# regulater.net
KiCad netlist of a schematic drawn in Altium Designer
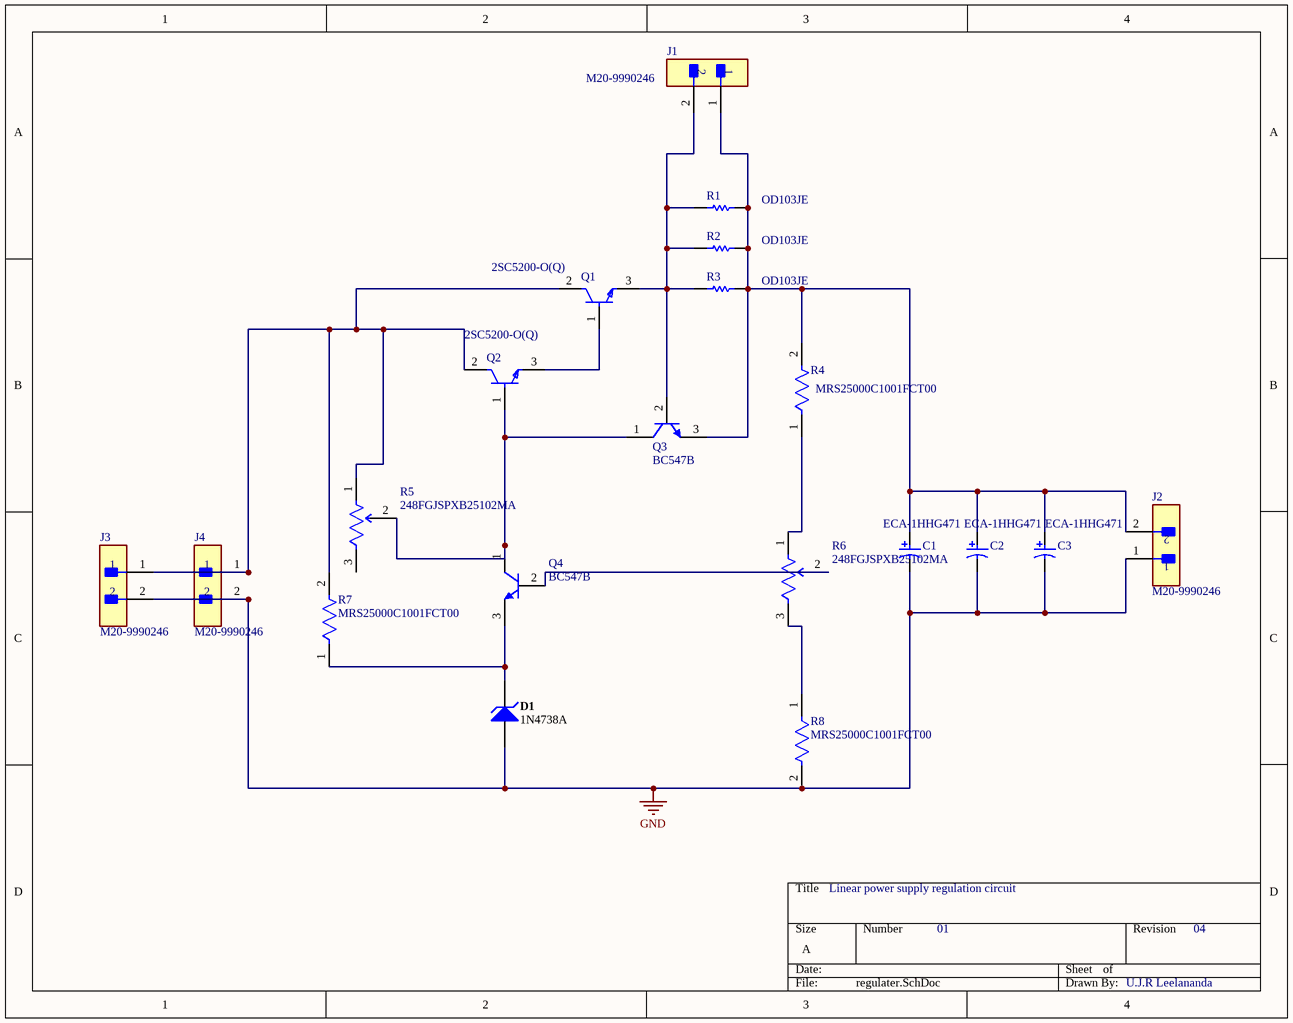
[diagram p0: regulater.SchDoc]

(export (version "E")
  (design (tool "Eeschema 10.0.6"))
  (components
    (comp (ref "C1")
      (value "ECA-1HHG471")
      (footprint "PNSC-CAP-10x20-P2")
      (description "Aluminum Electrolytic Capacitor, 470 uF, +/- 20%, 50 V, -55 to 105 degC, 2-Pin THD, RoHS, Bulk")
      (fields (field (name "MANUFACTURER") "Panasonic"))
      (libsource (lib "Altium Content Vault") (part "CAP-P-2"))
    )
    (comp (ref "C2")
      (value "ECA-1HHG471")
      (footprint "PNSC-CAP-10x20-P2")
      (description "Aluminum Electrolytic Capacitor, 470 uF, +/- 20%, 50 V, -55 to 105 degC, 2-Pin THD, RoHS, Bulk")
      (fields (field (name "MANUFACTURER") "Panasonic"))
      (libsource (lib "Altium Content Vault") (part "CAP-P-2"))
    )
    (comp (ref "C3")
      (value "ECA-1HHG471")
      (footprint "PNSC-CAP-10x20-P2")
      (description "Aluminum Electrolytic Capacitor, 470 uF, +/- 20%, 50 V, -55 to 105 degC, 2-Pin THD, RoHS, Bulk")
      (fields (field (name "MANUFACTURER") "Panasonic"))
      (libsource (lib "Altium Content Vault") (part "CAP-P-2"))
    )
    (comp (ref "D1")
      (value "1N4738A")
      (footprint "FAIR-DO-41-2_V")
      (description "Zener Diode, 8.2V, 1W, 5%, -65 to 200 degC, 2-Pin DO-41, Body 2.72 x 5.2 mm, RoHS")
      (fields (field (name "TOLERANCE") "5%") (field (name "MANUFACTURER") "Fairchild Semiconductor"))
      (libsource (lib "Altium Content Vault") (part "FAIR-DZEN-A1K2-2"))
    )
    (comp (ref "J1")
      (value "M20-9990246")
      (footprint "FP-M20-9990246-MFG")
      (description "CONN HEADER VERT 2POS 2.54MM")
      (fields
        (field (name "OCTOPART") "https://octopart.com/m20-9990246-harwin-2590635")
        (field (name "MANUFACTURER") "Harwin")
      )
      (libsource (lib "") (part "3bc925449376181038e59eaffc5286c_2"))
    )
    (comp (ref "J2")
      (value "M20-9990246")
      (footprint "FP-M20-9990246-MFG")
      (description "CONN HEADER VERT 2POS 2.54MM")
      (fields
        (field (name "OCTOPART") "https://octopart.com/m20-9990246-harwin-2590635")
        (field (name "MANUFACTURER") "Harwin")
      )
      (libsource (lib "") (part "3bc925449376181038e59eaffc5286c_1"))
    )
    (comp (ref "J3")
      (value "M20-9990246")
      (footprint "FP-M20-9990246-MFG")
      (description "CONN HEADER VERT 2POS 2.54MM")
      (fields
        (field (name "OCTOPART") "https://octopart.com/m20-9990246-harwin-2590635")
        (field (name "MANUFACTURER") "Harwin")
      )
      (libsource (lib "Altium Content Vault") (part "3bc925449376181038e59eaffc5286c"))
    )
    (comp (ref "J4")
      (value "M20-9990246")
      (footprint "FP-M20-9990246-MFG")
      (description "CONN HEADER VERT 2POS 2.54MM")
      (fields
        (field (name "OCTOPART") "https://octopart.com/m20-9990246-harwin-2590635")
        (field (name "MANUFACTURER") "Harwin")
      )
      (libsource (lib "Altium Content Vault") (part "3bc925449376181038e59eaffc5286c"))
    )
    (comp (ref "Q1")
      (value "2SC5200-O(Q)")
      (footprint "FP-2-21F1A-MFG")
      (description "TRANS NPN 230V 15A TO-3PL")
      (libsource (lib "Altium Content Vault") (part "00d3c44dadf19597ad74dcf16b45d25"))
    )
    (comp (ref "Q2")
      (value "2SC5200-O(Q)")
      (footprint "FP-2-21F1A-MFG")
      (description "TRANS NPN 230V 15A TO-3PL")
      (libsource (lib "Altium Content Vault") (part "00d3c44dadf19597ad74dcf16b45d25"))
    )
    (comp (ref "Q3")
      (value "BC547B")
      (footprint "ONSC-TO-92-3-29-11")
      (description "Amplifier Transistor, NPN Silicon, 3-Pin TO-92, Bulk Box")
      (fields (field (name "MANUFACTURER") "On Semiconductor"))
      (libsource (lib "Altium Content Vault") (part "ONSC-NPN-C1B2E3-3"))
    )
    (comp (ref "Q4")
      (value "BC547B")
      (footprint "ONSC-TO-92-3-29-11")
      (description "Amplifier Transistor, NPN Silicon, 3-Pin TO-92, Bulk Box")
      (fields (field (name "MANUFACTURER") "On Semiconductor"))
      (libsource (lib "Altium Content Vault") (part "ONSC-NPN-C1B2E3-3"))
    )
    (comp (ref "R1")
      (value "OD103JE")
      (footprint "OMTE-RES7X2.5-2")
      (fields (field (name "TOLERANCE") "±5%") (field (name "MANUFACTURER") "Ohmite"))
      (libsource (lib "Altium Content Vault") (part "RES-2"))
    )
    (comp (ref "R2")
      (value "OD103JE")
      (footprint "OMTE-RES7X2.5-2")
      (fields (field (name "TOLERANCE") "±5%") (field (name "MANUFACTURER") "Ohmite"))
      (libsource (lib "Altium Content Vault") (part "RES-2"))
    )
    (comp (ref "R3")
      (value "OD103JE")
      (footprint "OMTE-RES7X2.5-2")
      (fields (field (name "TOLERANCE") "±5%") (field (name "MANUFACTURER") "Ohmite"))
      (libsource (lib "Altium Content Vault") (part "RES-2"))
    )
    (comp (ref "R4")
      (value "MRS25000C1001FCT00")
      (footprint "FP-MRS25-MFG")
      (description "RES 1K OHM 0.6W 1% AXIAL")
      (fields (field (name "TOLERANCE") "1%"))
      (libsource (lib "Altium Content Vault") (part "1029c3af85768c4190bb7ad29bc67b5"))
    )
    (comp (ref "R5")
      (value "248FGJSPXB25102MA")
      (footprint "FP-248FGJSPXB25102MA-MFG")
      (description "POT PLASTIC LINEAR")
      (fields (field (name "TOLERANCE") "20%"))
      (libsource (lib "Altium Content Vault") (part "1187411b85b29beaefda66c4d54de6f"))
    )
    (comp (ref "R6")
      (value "248FGJSPXB25102MA")
      (footprint "FP-248FGJSPXB25102MA-MFG")
      (description "POT PLASTIC LINEAR")
      (fields (field (name "TOLERANCE") "20%"))
      (libsource (lib "Altium Content Vault") (part "1187411b85b29beaefda66c4d54de6f"))
    )
    (comp (ref "R7")
      (value "MRS25000C1001FCT00")
      (footprint "FP-MRS25-MFG")
      (description "RES 1K OHM 0.6W 1% AXIAL")
      (fields (field (name "TOLERANCE") "1%"))
      (libsource (lib "Altium Content Vault") (part "1029c3af85768c4190bb7ad29bc67b5"))
    )
    (comp (ref "R8")
      (value "MRS25000C1001FCT00")
      (footprint "FP-MRS25-MFG")
      (description "RES 1K OHM 0.6W 1% AXIAL")
      (fields (field (name "TOLERANCE") "1%"))
      (libsource (lib "Altium Content Vault") (part "1029c3af85768c4190bb7ad29bc67b5"))
    )
  )
  (nets
    (net (code "1") (name "GND") (class "Default")
      (node (ref "C1") (pin "2") (pinfunction "2_2") (pintype "passive"))
      (node (ref "C2") (pin "2") (pinfunction "2_2") (pintype "passive"))
      (node (ref "C3") (pin "2") (pinfunction "2_2") (pintype "passive"))
      (node (ref "D1") (pin "1") (pinfunction "A_1") (pintype "passive"))
      (node (ref "J2") (pin "1") (pinfunction "1_1") (pintype "passive"))
      (node (ref "J3") (pin "2") (pinfunction "2_2") (pintype "passive"))
      (node (ref "J4") (pin "2") (pinfunction "2_2") (pintype "passive"))
      (node (ref "R8") (pin "2") (pinfunction "2_2") (pintype "passive"))
    )
    (net (code "2") (name "Net-(D1-K)") (class "Default")
      (node (ref "D1") (pin "2") (pinfunction "K_2") (pintype "passive"))
      (node (ref "Q4") (pin "3") (pinfunction "E_3") (pintype "passive"))
      (node (ref "R7") (pin "1") (pinfunction "1_1") (pintype "passive"))
    )
    (net (code "3") (name "Net-(Q1-B)") (class "Default")
      (node (ref "Q1") (pin "1") (pinfunction "B_1") (pintype "passive"))
      (node (ref "Q2") (pin "3") (pinfunction "E_3") (pintype "passive"))
    )
    (net (code "4") (name "Net-(Q1-C)") (class "Default")
      (node (ref "J3") (pin "1") (pinfunction "1_1") (pintype "passive"))
      (node (ref "J4") (pin "1") (pinfunction "1_1") (pintype "passive"))
      (node (ref "Q1") (pin "2") (pinfunction "C_2") (pintype "passive"))
      (node (ref "Q2") (pin "2") (pinfunction "C_2") (pintype "passive"))
      (node (ref "R5") (pin "1") (pinfunction "1_1") (pintype "passive"))
      (node (ref "R7") (pin "2") (pinfunction "2_2") (pintype "passive"))
    )
    (net (code "5") (name "Net-(Q1-E)") (class "Default")
      (node (ref "J1") (pin "2") (pinfunction "2_2") (pintype "passive"))
      (node (ref "Q1") (pin "3") (pinfunction "E_3") (pintype "passive"))
      (node (ref "Q3") (pin "2") (pinfunction "B_2") (pintype "passive"))
      (node (ref "R1") (pin "1") (pinfunction "1_1") (pintype "passive"))
      (node (ref "R2") (pin "1") (pinfunction "1_1") (pintype "passive"))
      (node (ref "R3") (pin "1") (pinfunction "1_1") (pintype "passive"))
    )
    (net (code "6") (name "Net-(Q2-B)") (class "Default")
      (node (ref "Q2") (pin "1") (pinfunction "B_1") (pintype "passive"))
      (node (ref "Q3") (pin "1") (pinfunction "C_1") (pintype "passive"))
      (node (ref "Q4") (pin "1") (pinfunction "C_1") (pintype "passive"))
      (node (ref "R5") (pin "2") (pinfunction "CW_2") (pintype "passive"))
    )
    (net (code "7") (name "Net-(Q3-E)") (class "Default")
      (node (ref "C1") (pin "1") (pinfunction "1_1") (pintype "passive"))
      (node (ref "C2") (pin "1") (pinfunction "1_1") (pintype "passive"))
      (node (ref "C3") (pin "1") (pinfunction "1_1") (pintype "passive"))
      (node (ref "J1") (pin "1") (pinfunction "1_1") (pintype "passive"))
      (node (ref "J2") (pin "2") (pinfunction "2_2") (pintype "passive"))
      (node (ref "Q3") (pin "3") (pinfunction "E_3") (pintype "passive"))
      (node (ref "R1") (pin "2") (pinfunction "2_2") (pintype "passive"))
      (node (ref "R2") (pin "2") (pinfunction "2_2") (pintype "passive"))
      (node (ref "R3") (pin "2") (pinfunction "2_2") (pintype "passive"))
      (node (ref "R4") (pin "2") (pinfunction "2_2") (pintype "passive"))
    )
    (net (code "8") (name "Net-(Q4-B)") (class "Default")
      (node (ref "Q4") (pin "2") (pinfunction "B_2") (pintype "passive"))
      (node (ref "R6") (pin "2") (pinfunction "CW_2") (pintype "passive"))
    )
    (net (code "9") (name "Net-(R4-Pad1)") (class "Default")
      (node (ref "R4") (pin "1") (pinfunction "1_1") (pintype "passive"))
      (node (ref "R6") (pin "1") (pinfunction "1_1") (pintype "passive"))
    )
    (net (code "10") (name "Net-(R6-Pad3)") (class "Default")
      (node (ref "R6") (pin "3") (pinfunction "3_3") (pintype "passive"))
      (node (ref "R8") (pin "1") (pinfunction "1_1") (pintype "passive"))
    )
    (net (code "11") (name "unconnected-(R5-Pad3)") (class "Default")
      (node (ref "R5") (pin "3") (pinfunction "3_3") (pintype "passive"))
    )
  )
)
